# ATTAMI-Shield-stepperDriver.net
KiCad netlist of a schematic drawn in EAGLE
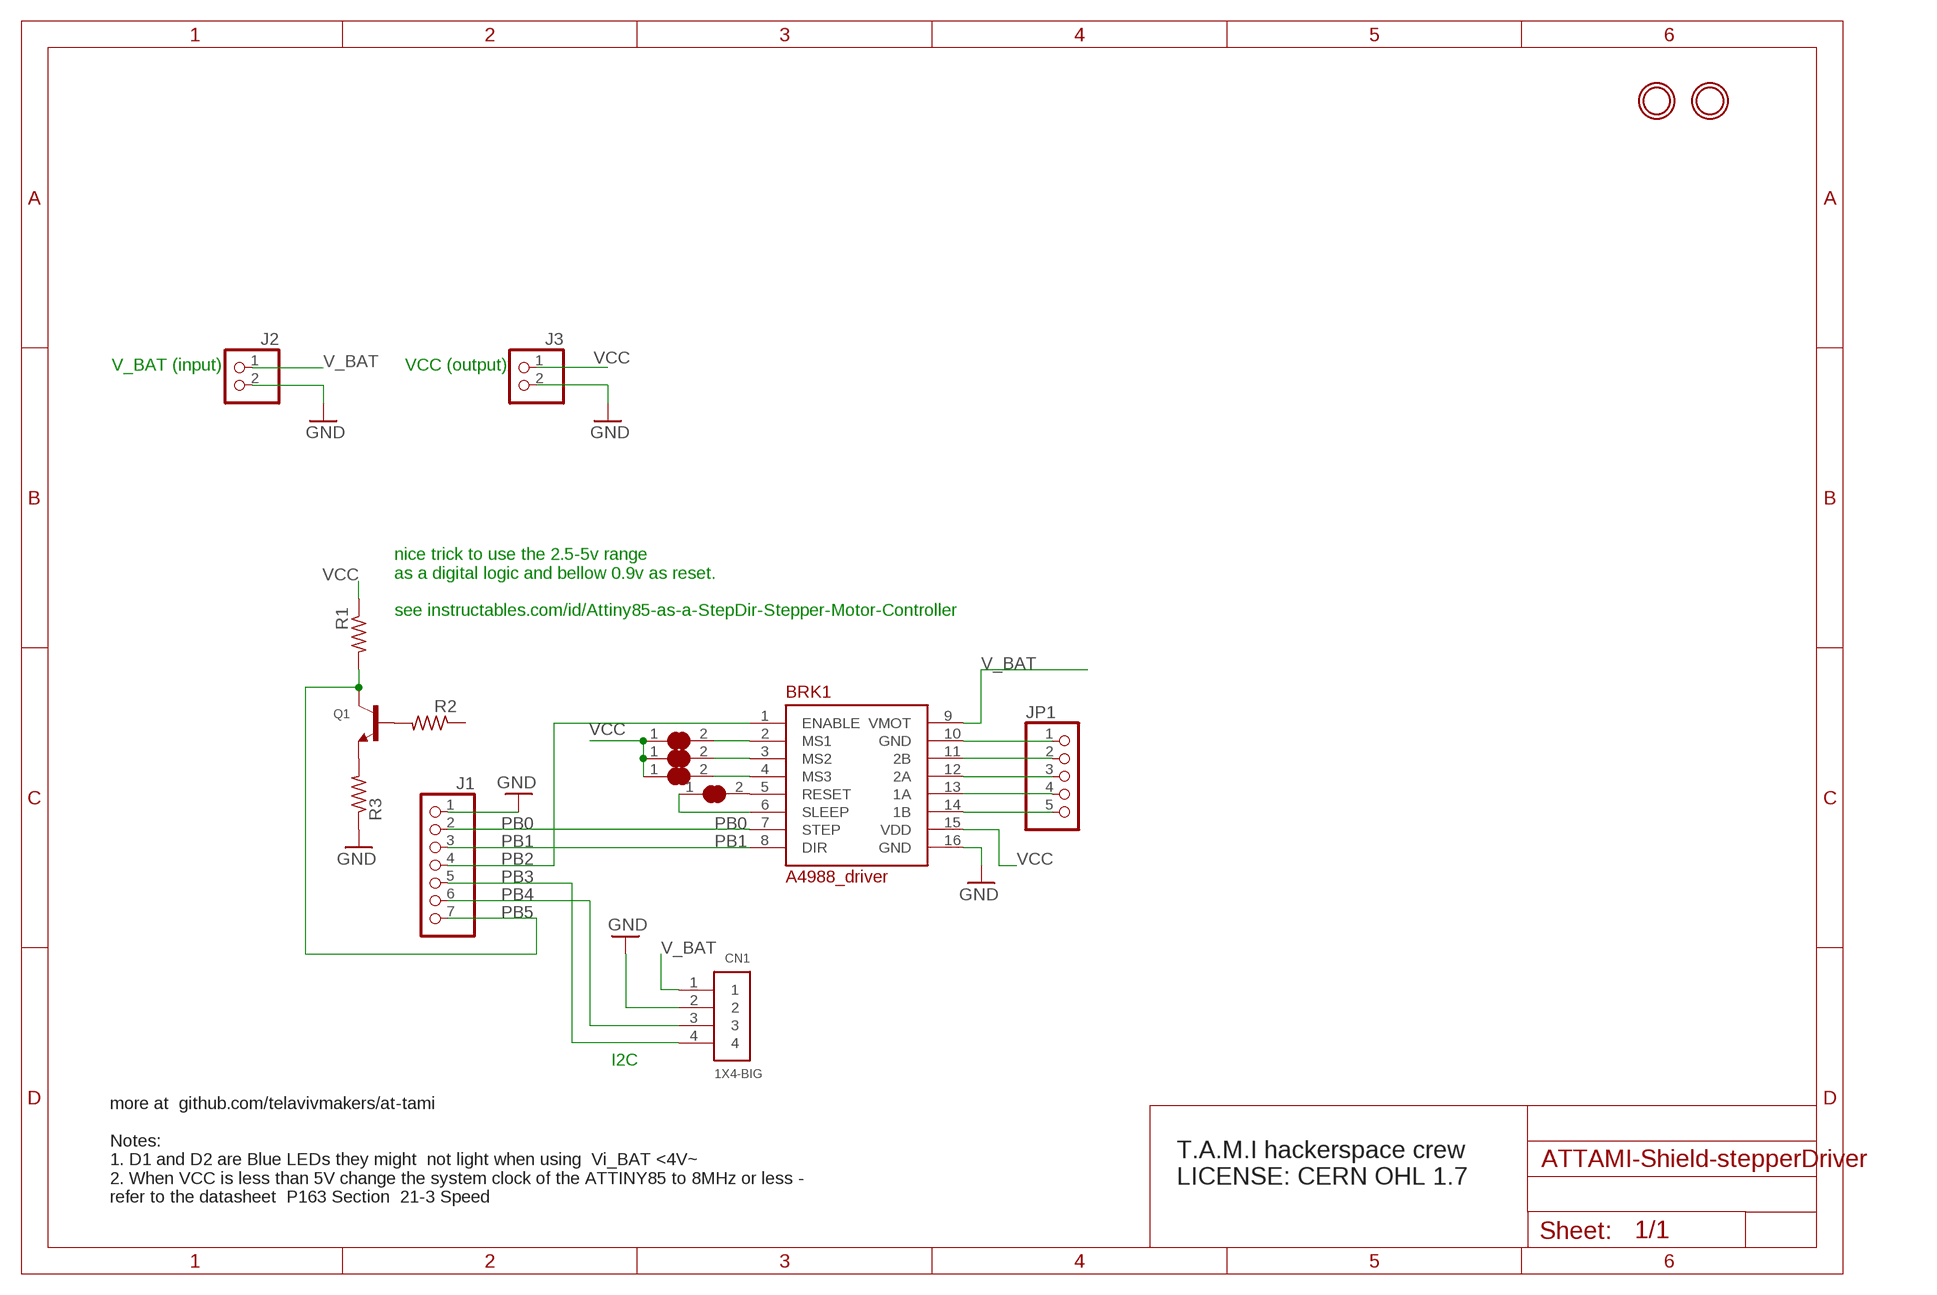
[diagram p0: schematic, sheet 1]

(export (version "E")
  (design (tool "Eeschema 10.0.6"))
  (components
    (comp (ref "BRK1")
      (value "A4988_driver")
      (footprint "eagle-import:DIL16")
      (libsource (lib "eagle-import") (part "A4988_DRIVER"))
    )
    (comp (ref "CN1")
      (value "1X4-BIG")
      (footprint "eagle-import:1X04-BIG")
      (libsource (lib "eagle-import") (part "1X4-BIG"))
    )
    (comp (ref "J1")
      (value "HEADER-1X7ROUND")
      (footprint "eagle-import:1X07_ROUND")
      (libsource (lib "eagle-import") (part "HEADER-1X7ROUND"))
    )
    (comp (ref "J2")
      (value "HEADER-1X2ROUND")
      (footprint "eagle-import:1X02_ROUND")
      (libsource (lib "eagle-import") (part "HEADER-1X2ROUND"))
    )
    (comp (ref "J3")
      (value "HEADER-1X2ROUND")
      (footprint "eagle-import:1X02_ROUND")
      (libsource (lib "eagle-import") (part "HEADER-1X2ROUND"))
    )
    (comp (ref "JP1")
      (value "HEADER-1X5")
      (footprint "eagle-import:1X05_OVAL")
      (libsource (lib "eagle-import") (part "HEADER-1X5"))
    )
    (comp (ref "Q1")
      (value "TRANSISTOR_NPNWAVE")
      (footprint "eagle-import:SOT23-W")
      (libsource (lib "eagle-import") (part "TRANSISTOR_NPNWAVE"))
    )
    (comp (ref "R1")
      (value "R-US_R0805")
      (footprint "eagle-import:R0805")
      (libsource (lib "eagle-import") (part "R-US_R0805"))
    )
    (comp (ref "R2")
      (value "R-US_R0805")
      (footprint "eagle-import:R0805")
      (libsource (lib "eagle-import") (part "R-US_R0805"))
    )
    (comp (ref "R3")
      (value "R-US_R0805")
      (footprint "eagle-import:R0805")
      (libsource (lib "eagle-import") (part "R-US_R0805"))
    )
    (comp (ref "SJ1")
      (value "SOLDERJUMPER_CLOSED")
      (footprint "eagle-import:SOLDERJUMPER_CLOSEDWIRE")
      (libsource (lib "eagle-import") (part "SOLDERJUMPER_CLOSED"))
    )
    (comp (ref "SJ2")
      (value "SOLDERJUMPER_CLOSED")
      (footprint "eagle-import:SOLDERJUMPER_CLOSEDWIRE")
      (libsource (lib "eagle-import") (part "SOLDERJUMPER_CLOSED"))
    )
    (comp (ref "SJ3")
      (value "SOLDERJUMPER_CLOSED")
      (footprint "eagle-import:SOLDERJUMPER_CLOSEDWIRE")
      (libsource (lib "eagle-import") (part "SOLDERJUMPER_CLOSED"))
    )
    (comp (ref "SJ4")
      (value "SOLDERJUMPER_CLOSED")
      (footprint "eagle-import:SOLDERJUMPER_CLOSEDWIRE")
      (libsource (lib "eagle-import") (part "SOLDERJUMPER_CLOSED"))
    )
    (comp (ref "U$1")
      (value "MOUNTINGHOLE2.0")
      (footprint "eagle-import:MOUNTINGHOLE_2.0_PLATED")
      (libsource (lib "eagle-import") (part "MOUNTINGHOLE2.0"))
    )
    (comp (ref "U$2")
      (value "MOUNTINGHOLE2.0")
      (footprint "eagle-import:MOUNTINGHOLE_2.0_PLATED")
      (libsource (lib "eagle-import") (part "MOUNTINGHOLE2.0"))
    )
  )
  (nets
    (net (code "1") (name "/PB0") (class "Default")
      (node (ref "BRK1") (pin "7") (pinfunction "STEP_7") (pintype "bidirectional"))
      (node (ref "J1") (pin "2") (pinfunction "2_2") (pintype "passive"))
    )
    (net (code "2") (name "/PB1") (class "Default")
      (node (ref "BRK1") (pin "8") (pinfunction "DIR_8") (pintype "bidirectional"))
      (node (ref "J1") (pin "3") (pinfunction "3_3") (pintype "passive"))
    )
    (net (code "3") (name "/PB2") (class "Default")
      (node (ref "BRK1") (pin "1") (pinfunction "ENABLE_1") (pintype "bidirectional"))
      (node (ref "J1") (pin "4") (pinfunction "4_4") (pintype "passive"))
    )
    (net (code "4") (name "/PB3") (class "Default")
      (node (ref "CN1") (pin "4") (pinfunction "4_4") (pintype "bidirectional"))
      (node (ref "J1") (pin "5") (pinfunction "5_5") (pintype "passive"))
    )
    (net (code "5") (name "/PB4") (class "Default")
      (node (ref "CN1") (pin "3") (pinfunction "3_3") (pintype "bidirectional"))
      (node (ref "J1") (pin "6") (pinfunction "6_6") (pintype "passive"))
    )
    (net (code "6") (name "/PB5") (class "Default")
      (node (ref "J1") (pin "7") (pinfunction "7_7") (pintype "passive"))
      (node (ref "Q1") (pin "3") (pinfunction "C_3") (pintype "passive"))
      (node (ref "R1") (pin "2") (pinfunction "2_2") (pintype "passive"))
    )
    (net (code "7") (name "/VCC") (class "Default")
      (node (ref "BRK1") (pin "15") (pinfunction "VDD_15") (pintype "bidirectional"))
      (node (ref "J3") (pin "1") (pinfunction "1_1") (pintype "passive"))
      (node (ref "R1") (pin "1") (pinfunction "1_1") (pintype "passive"))
      (node (ref "SJ1") (pin "1") (pinfunction "1_1") (pintype "passive"))
      (node (ref "SJ2") (pin "1") (pinfunction "1_1") (pintype "passive"))
      (node (ref "SJ3") (pin "1") (pinfunction "1_1") (pintype "passive"))
    )
    (net (code "8") (name "/V_BAT") (class "Default")
      (node (ref "BRK1") (pin "9") (pinfunction "VMOT_9") (pintype "bidirectional"))
      (node (ref "CN1") (pin "1") (pinfunction "1_1") (pintype "bidirectional"))
      (node (ref "J2") (pin "1") (pinfunction "1_1") (pintype "passive"))
    )
    (net (code "9") (name "GND") (class "Default")
      (node (ref "BRK1") (pin "10") (pinfunction "GND_10") (pintype "bidirectional"))
      (node (ref "BRK1") (pin "16") (pinfunction "GND_16") (pintype "bidirectional"))
      (node (ref "CN1") (pin "2") (pinfunction "2_2") (pintype "bidirectional"))
      (node (ref "J1") (pin "1") (pinfunction "1_1") (pintype "passive"))
      (node (ref "J2") (pin "2") (pinfunction "2_2") (pintype "passive"))
      (node (ref "J3") (pin "2") (pinfunction "2_2") (pintype "passive"))
      (node (ref "JP1") (pin "1") (pinfunction "1_1") (pintype "passive"))
      (node (ref "R3") (pin "1") (pinfunction "1_1") (pintype "passive"))
    )
    (net (code "10") (name "Net-(BRK1-1A)") (class "Default")
      (node (ref "BRK1") (pin "13") (pinfunction "1A_13") (pintype "bidirectional"))
      (node (ref "JP1") (pin "4") (pinfunction "4_4") (pintype "passive"))
    )
    (net (code "11") (name "Net-(BRK1-1B)") (class "Default")
      (node (ref "BRK1") (pin "14") (pinfunction "1B_14") (pintype "bidirectional"))
      (node (ref "JP1") (pin "5") (pinfunction "5_5") (pintype "passive"))
    )
    (net (code "12") (name "Net-(BRK1-2A)") (class "Default")
      (node (ref "BRK1") (pin "12") (pinfunction "2A_12") (pintype "bidirectional"))
      (node (ref "JP1") (pin "3") (pinfunction "3_3") (pintype "passive"))
    )
    (net (code "13") (name "Net-(BRK1-2B)") (class "Default")
      (node (ref "BRK1") (pin "11") (pinfunction "2B_11") (pintype "bidirectional"))
      (node (ref "JP1") (pin "2") (pinfunction "2_2") (pintype "passive"))
    )
    (net (code "14") (name "Net-(BRK1-MS1)") (class "Default")
      (node (ref "BRK1") (pin "2") (pinfunction "MS1_2") (pintype "bidirectional"))
      (node (ref "SJ3") (pin "2") (pinfunction "2_2") (pintype "passive"))
    )
    (net (code "15") (name "Net-(BRK1-MS2)") (class "Default")
      (node (ref "BRK1") (pin "3") (pinfunction "MS2_3") (pintype "bidirectional"))
      (node (ref "SJ2") (pin "2") (pinfunction "2_2") (pintype "passive"))
    )
    (net (code "16") (name "Net-(BRK1-MS3)") (class "Default")
      (node (ref "BRK1") (pin "4") (pinfunction "MS3_4") (pintype "bidirectional"))
      (node (ref "SJ1") (pin "2") (pinfunction "2_2") (pintype "passive"))
    )
    (net (code "17") (name "Net-(BRK1-RESET)") (class "Default")
      (node (ref "BRK1") (pin "5") (pinfunction "RESET_5") (pintype "bidirectional"))
      (node (ref "SJ4") (pin "2") (pinfunction "2_2") (pintype "passive"))
    )
    (net (code "18") (name "Net-(BRK1-SLEEP)") (class "Default")
      (node (ref "BRK1") (pin "6") (pinfunction "SLEEP_6") (pintype "bidirectional"))
      (node (ref "SJ4") (pin "1") (pinfunction "1_1") (pintype "passive"))
    )
    (net (code "19") (name "Net-(Q1-B)") (class "Default")
      (node (ref "Q1") (pin "1") (pinfunction "B_1") (pintype "passive"))
      (node (ref "R2") (pin "2") (pinfunction "2_2") (pintype "passive"))
    )
    (net (code "20") (name "Net-(Q1-E)") (class "Default")
      (node (ref "Q1") (pin "2") (pinfunction "E_2") (pintype "passive"))
      (node (ref "R3") (pin "2") (pinfunction "2_2") (pintype "passive"))
    )
    (net (code "21") (name "unconnected-(R2-Pad1)") (class "Default")
      (node (ref "R2") (pin "1") (pinfunction "1_1") (pintype "passive"))
    )
  )
)
